# Ethernet.net
KiCad netlist of a schematic drawn in Altium Designer
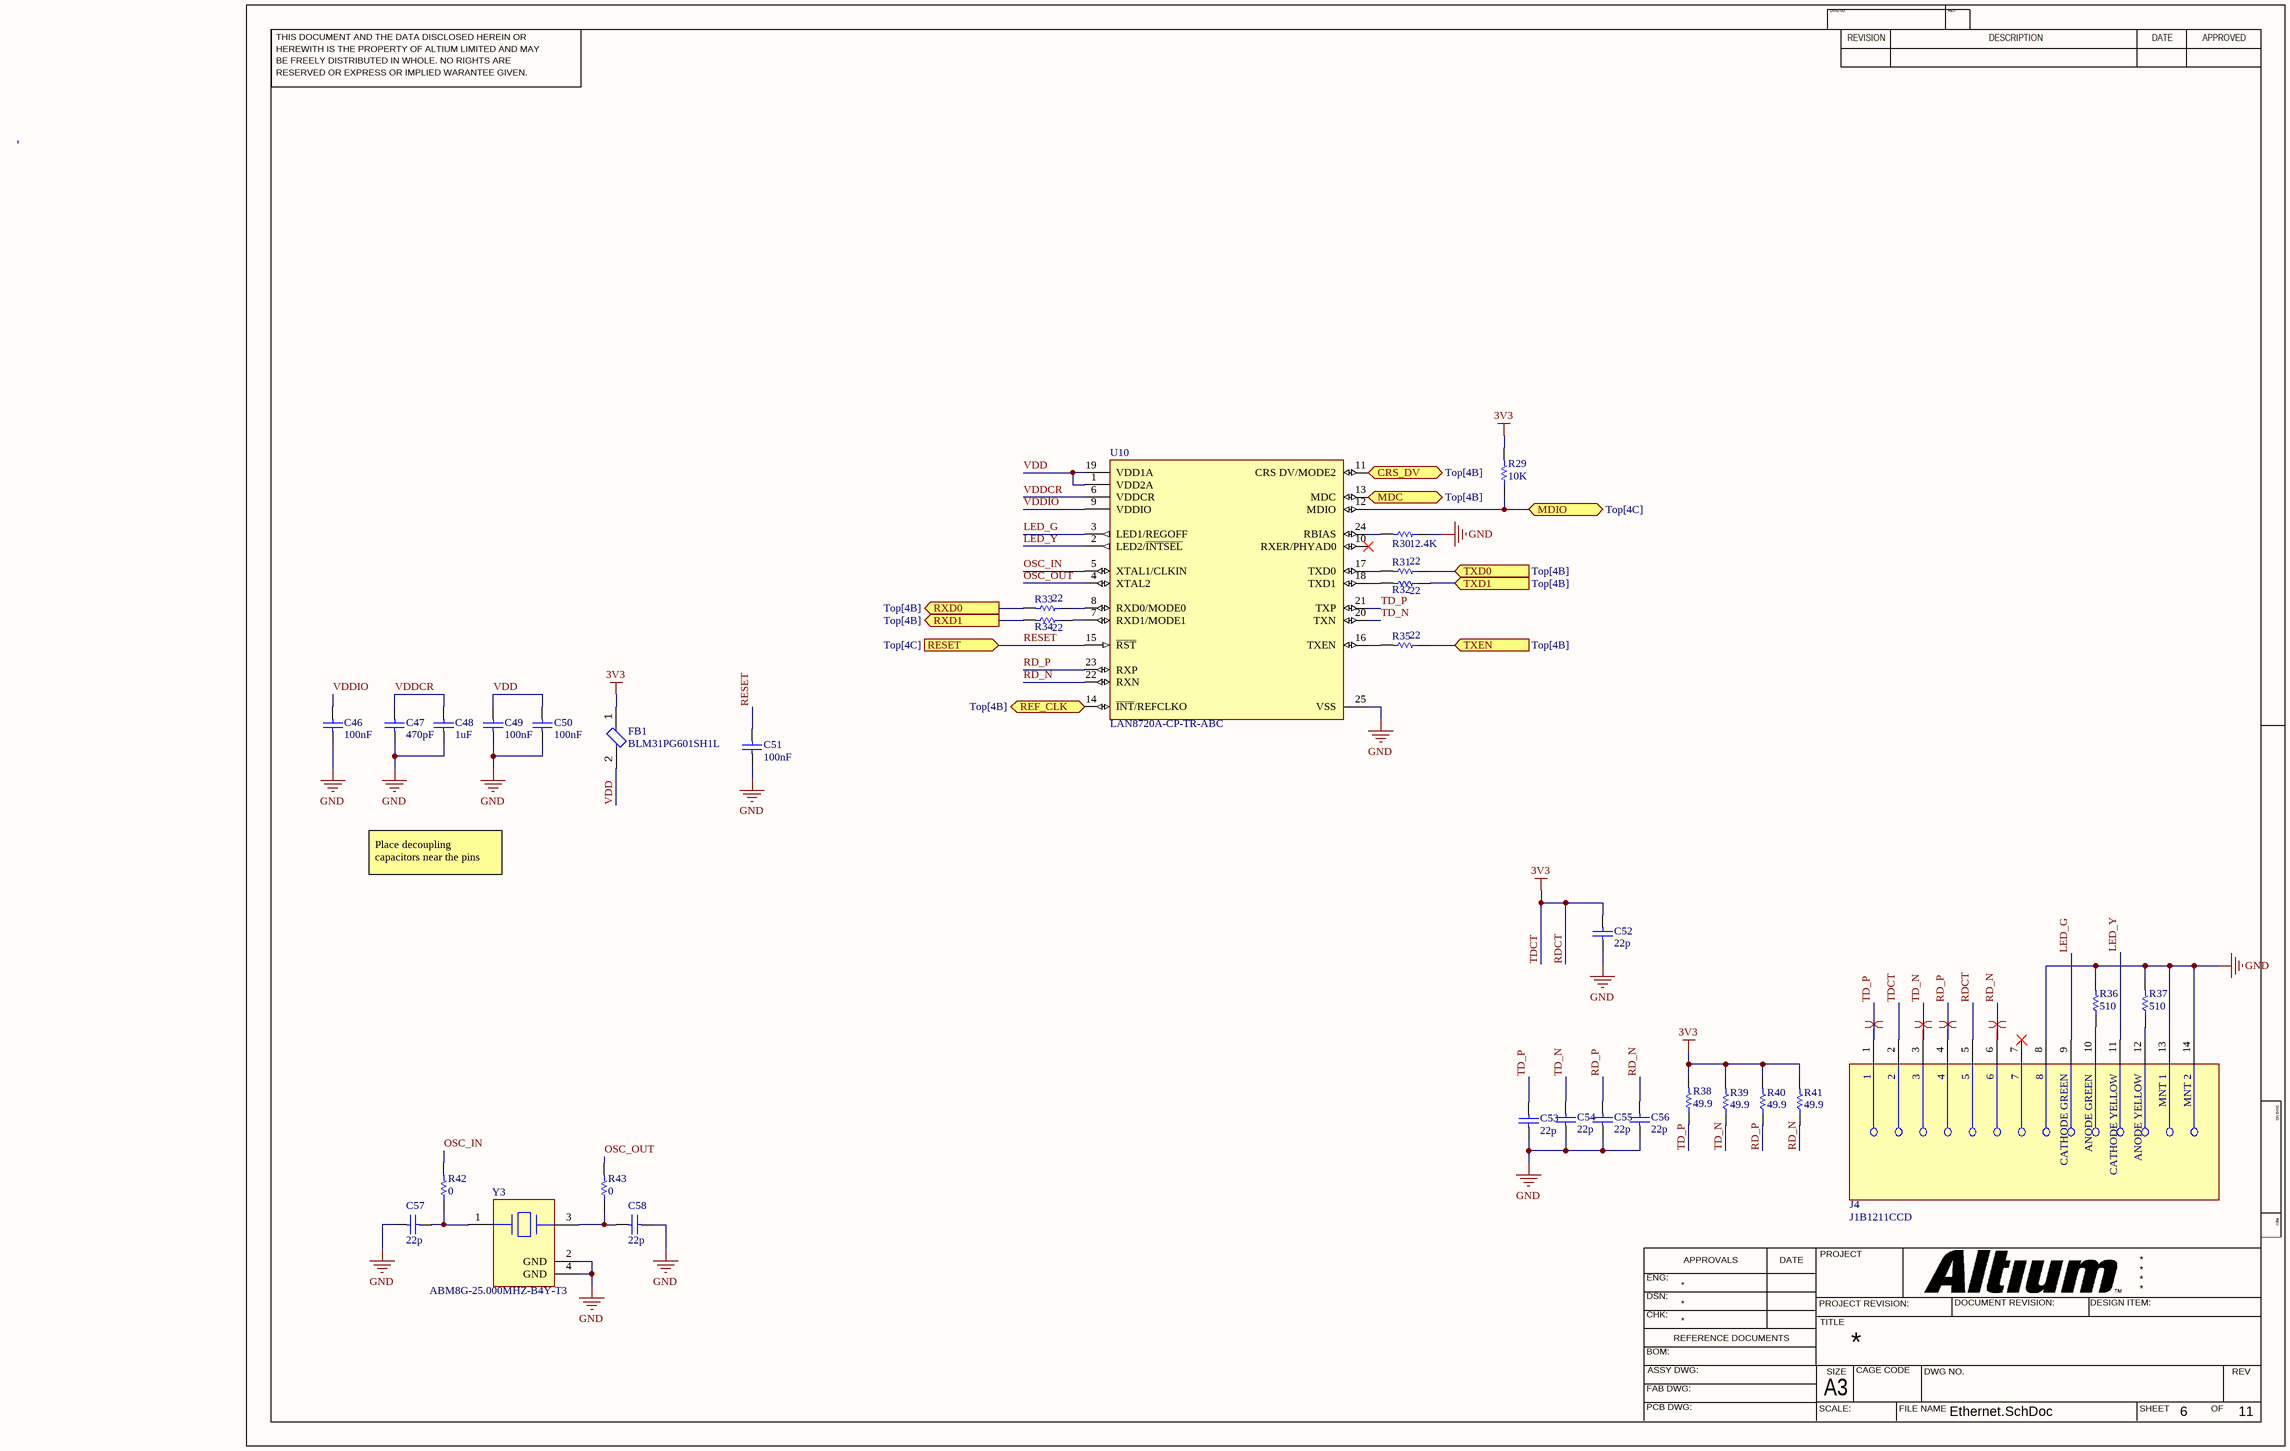
[diagram p0: Ethernet.SchDoc]

(export (version "E")
  (design (tool "Eeschema 10.0.6"))
  (components
    (comp (ref "C46")
      (value "100nF")
      (description "Capacitor")
      (libsource (lib "Simulation Generic Components") (part "Capacitor"))
    )
    (comp (ref "C47")
      (value "470pF")
      (description "Capacitor")
      (libsource (lib "Simulation Generic Components") (part "Capacitor"))
    )
    (comp (ref "C48")
      (value "1uF")
      (description "Capacitor")
      (libsource (lib "Simulation Generic Components") (part "Capacitor"))
    )
    (comp (ref "C49")
      (value "100nF")
      (description "Capacitor")
      (libsource (lib "Simulation Generic Components") (part "Capacitor"))
    )
    (comp (ref "C50")
      (value "100nF")
      (description "Capacitor")
      (libsource (lib "Simulation Generic Components") (part "Capacitor"))
    )
    (comp (ref "C51")
      (value "100nF")
      (description "Capacitor")
      (libsource (lib "Simulation Generic Components") (part "Capacitor"))
    )
    (comp (ref "C52")
      (value "22p")
      (description "Capacitor")
      (libsource (lib "Simulation Generic Components") (part "Capacitor"))
    )
    (comp (ref "C53")
      (value "22p")
      (description "Capacitor")
      (libsource (lib "Simulation Generic Components") (part "Capacitor"))
    )
    (comp (ref "C54")
      (value "22p")
      (description "Capacitor")
      (libsource (lib "Simulation Generic Components") (part "Capacitor"))
    )
    (comp (ref "C55")
      (value "22p")
      (description "Capacitor")
      (libsource (lib "Simulation Generic Components") (part "Capacitor"))
    )
    (comp (ref "C56")
      (value "22p")
      (description "Capacitor")
      (libsource (lib "Simulation Generic Components") (part "Capacitor"))
    )
    (comp (ref "C57")
      (value "22p")
      (description "Capacitor")
      (libsource (lib "Simulation Generic Components") (part "Capacitor"))
    )
    (comp (ref "C58")
      (value "22p")
      (description "Capacitor")
      (libsource (lib "Simulation Generic Components") (part "Capacitor"))
    )
    (comp (ref "FB1")
      (value "BLM31PG601SH1L")
      (footprint "FP-BLM31-0_2-t1_1-MFG")
      (description "Chip Ferrite Bead Array, 1206, 600Ω @ 100MHz, 0.08Ω, 25%, 1.5A")
      (fields (field (name "TOLERANCE") "25%"))
      (libsource (lib "Altium Content Vault") (part "5f30dd21d616792df468990f7003faa"))
    )
    (comp (ref "J4")
      (value "J1B1211CCD")
      (footprint "FP-J1B1211CCD-MFG")
      (description "CONN JACK 1PORT 100 BASE-T PCB")
      (libsource (lib "Altium Content Vault") (part "043a9053fb366fe6dc2bf5dbfb72c80"))
    )
    (comp (ref "R29")
      (value "10K")
      (description "Resistor")
      (libsource (lib "Simulation Generic Components") (part "Resistor"))
    )
    (comp (ref "R30")
      (value "12.4K")
      (description "Resistor")
      (libsource (lib "Simulation Generic Components") (part "Resistor"))
    )
    (comp (ref "R31")
      (value "22")
      (description "Resistor")
      (libsource (lib "Simulation Generic Components") (part "Resistor"))
    )
    (comp (ref "R32")
      (value "22")
      (description "Resistor")
      (libsource (lib "Simulation Generic Components") (part "Resistor"))
    )
    (comp (ref "R33")
      (value "22")
      (description "Resistor")
      (libsource (lib "Simulation Generic Components") (part "Resistor"))
    )
    (comp (ref "R34")
      (value "22")
      (description "Resistor")
      (libsource (lib "Simulation Generic Components") (part "Resistor"))
    )
    (comp (ref "R35")
      (value "22")
      (description "Resistor")
      (libsource (lib "Simulation Generic Components") (part "Resistor"))
    )
    (comp (ref "R36")
      (value "510")
      (description "Resistor")
      (libsource (lib "Simulation Generic Components") (part "Resistor"))
    )
    (comp (ref "R37")
      (value "510")
      (description "Resistor")
      (libsource (lib "Simulation Generic Components") (part "Resistor"))
    )
    (comp (ref "R38")
      (value "49.9")
      (description "Resistor")
      (libsource (lib "Simulation Generic Components") (part "Resistor"))
    )
    (comp (ref "R39")
      (value "49.9")
      (description "Resistor")
      (libsource (lib "Simulation Generic Components") (part "Resistor"))
    )
    (comp (ref "R40")
      (value "49.9")
      (description "Resistor")
      (libsource (lib "Simulation Generic Components") (part "Resistor"))
    )
    (comp (ref "R41")
      (value "49.9")
      (description "Resistor")
      (libsource (lib "Simulation Generic Components") (part "Resistor"))
    )
    (comp (ref "R42")
      (value "0")
      (description "Resistor")
      (libsource (lib "Simulation Generic Components") (part "Resistor"))
    )
    (comp (ref "R43")
      (value "0")
      (description "Resistor")
      (libsource (lib "Simulation Generic Components") (part "Resistor"))
    )
    (comp (ref "U10")
      (value "LAN8720A-CP-TR-ABC")
      (footprint "FP-24-S4QFN-4x4B-0_5P-IPC_B")
      (description "IC TRANSCEIVER FULL 2/2 24SQFN")
      (libsource (lib "Altium Content Vault") (part "9fc9cb1ae97c4b8e8fc1e70f7f78ae1"))
    )
    (comp (ref "Y3")
      (value "ABM8G-25.000MHZ-B4Y-T3")
      (footprint "FP-ABM8G-MFG")
      (description "Crystal 25MHz ±30ppm (Tol) ±30ppm (Stability) 10pF FUND 60Ω 4-Pin SMD T/R")
      (fields (field (name "TOLERANCE") "30ppm"))
      (libsource (lib "Altium Content Vault") (part "48e526d86b7f2615d98721063c72f49"))
    )
  )
  (nets
    (net (code "1") (name "/CRS_DV") (class "Default")
      (node (ref "U10") (pin "11") (pinfunction "CRS_DV/MODE2_11") (pintype "bidirectional"))
    )
    (net (code "2") (name "/LED_G") (class "Default")
      (node (ref "J4") (pin "9") (pinfunction "CATHODE_GREEN_9") (pintype "passive"))
      (node (ref "U10") (pin "3") (pinfunction "LED1/REGOFF_3") (pintype "output"))
    )
    (net (code "3") (name "/LED_Y") (class "Default")
      (node (ref "J4") (pin "11") (pinfunction "CATHODE_YELLOW_11") (pintype "passive"))
      (node (ref "U10") (pin "2") (pinfunction "LED2/~{INTSEL}_2") (pintype "output"))
    )
    (net (code "4") (name "/MDC") (class "Default")
      (node (ref "U10") (pin "13") (pinfunction "MDC_13") (pintype "bidirectional"))
    )
    (net (code "5") (name "/MDIO") (class "Default")
      (node (ref "R29") (pin "1") (pinfunction "1_1") (pintype "passive"))
      (node (ref "U10") (pin "12") (pinfunction "MDIO_12") (pintype "bidirectional"))
    )
    (net (code "6") (name "/OSC_IN") (class "Default")
      (node (ref "R42") (pin "2") (pinfunction "2_2") (pintype "passive"))
      (node (ref "U10") (pin "5") (pinfunction "XTAL1/CLKIN_5") (pintype "bidirectional"))
    )
    (net (code "7") (name "/OSC_OUT") (class "Default")
      (node (ref "R43") (pin "2") (pinfunction "2_2") (pintype "passive"))
      (node (ref "U10") (pin "4") (pinfunction "XTAL2_4") (pintype "bidirectional"))
    )
    (net (code "8") (name "/RD_N") (class "Default")
      (node (ref "C56") (pin "2") (pinfunction "2_2") (pintype "passive"))
      (node (ref "J4") (pin "6") (pinfunction "6_6") (pintype "passive"))
      (node (ref "R41") (pin "1") (pinfunction "1_1") (pintype "passive"))
      (node (ref "U10") (pin "22") (pinfunction "RXN_22") (pintype "bidirectional"))
    )
    (net (code "9") (name "/RD_P") (class "Default")
      (node (ref "C55") (pin "2") (pinfunction "2_2") (pintype "passive"))
      (node (ref "J4") (pin "4") (pinfunction "4_4") (pintype "passive"))
      (node (ref "R40") (pin "1") (pinfunction "1_1") (pintype "passive"))
      (node (ref "U10") (pin "23") (pinfunction "RXP_23") (pintype "bidirectional"))
    )
    (net (code "10") (name "/REF_CLK") (class "Default")
      (node (ref "U10") (pin "14") (pinfunction "~{INT}/REFCLKO_14") (pintype "bidirectional"))
    )
    (net (code "11") (name "/RESET") (class "Default")
      (node (ref "C51") (pin "2") (pinfunction "2_2") (pintype "passive"))
      (node (ref "U10") (pin "15") (pinfunction "~{RST}_15") (pintype "input"))
    )
    (net (code "12") (name "/RXD0") (class "Default")
      (node (ref "R33") (pin "2") (pinfunction "2_2") (pintype "passive"))
    )
    (net (code "13") (name "/RXD1") (class "Default")
      (node (ref "R34") (pin "2") (pinfunction "2_2") (pintype "passive"))
    )
    (net (code "14") (name "/TD_N") (class "Default")
      (node (ref "C54") (pin "2") (pinfunction "2_2") (pintype "passive"))
      (node (ref "J4") (pin "3") (pinfunction "3_3") (pintype "passive"))
      (node (ref "R39") (pin "1") (pinfunction "1_1") (pintype "passive"))
      (node (ref "U10") (pin "20") (pinfunction "TXN_20") (pintype "bidirectional"))
    )
    (net (code "15") (name "/TD_P") (class "Default")
      (node (ref "C53") (pin "2") (pinfunction "2_2") (pintype "passive"))
      (node (ref "J4") (pin "1") (pinfunction "1_1") (pintype "passive"))
      (node (ref "R38") (pin "1") (pinfunction "1_1") (pintype "passive"))
      (node (ref "U10") (pin "21") (pinfunction "TXP_21") (pintype "bidirectional"))
    )
    (net (code "16") (name "/TXD0") (class "Default")
      (node (ref "R31") (pin "1") (pinfunction "1_1") (pintype "passive"))
    )
    (net (code "17") (name "/TXD1") (class "Default")
      (node (ref "R32") (pin "1") (pinfunction "1_1") (pintype "passive"))
    )
    (net (code "18") (name "/TXEN") (class "Default")
      (node (ref "R35") (pin "1") (pinfunction "1_1") (pintype "passive"))
    )
    (net (code "19") (name "/VDD") (class "Default")
      (node (ref "C49") (pin "2") (pinfunction "2_2") (pintype "passive"))
      (node (ref "C50") (pin "2") (pinfunction "2_2") (pintype "passive"))
      (node (ref "FB1") (pin "2") (pinfunction "2_2") (pintype "passive"))
      (node (ref "U10") (pin "1") (pinfunction "VDD2A_1") (pintype "power_in"))
      (node (ref "U10") (pin "19") (pinfunction "VDD1A_19") (pintype "power_in"))
    )
    (net (code "20") (name "/VDDCR") (class "Default")
      (node (ref "C47") (pin "2") (pinfunction "2_2") (pintype "passive"))
      (node (ref "C48") (pin "2") (pinfunction "2_2") (pintype "passive"))
      (node (ref "U10") (pin "6") (pinfunction "VDDCR_6") (pintype "power_in"))
    )
    (net (code "21") (name "/VDDIO") (class "Default")
      (node (ref "C46") (pin "2") (pinfunction "2_2") (pintype "passive"))
      (node (ref "U10") (pin "9") (pinfunction "VDDIO_9") (pintype "power_in"))
    )
    (net (code "22") (name "3V3") (class "Default")
      (node (ref "C52") (pin "2") (pinfunction "2_2") (pintype "passive"))
      (node (ref "FB1") (pin "1") (pinfunction "1_1") (pintype "passive"))
      (node (ref "J4") (pin "2") (pinfunction "2_2") (pintype "passive"))
      (node (ref "J4") (pin "5") (pinfunction "5_5") (pintype "passive"))
      (node (ref "R29") (pin "2") (pinfunction "2_2") (pintype "passive"))
      (node (ref "R38") (pin "2") (pinfunction "2_2") (pintype "passive"))
      (node (ref "R39") (pin "2") (pinfunction "2_2") (pintype "passive"))
      (node (ref "R40") (pin "2") (pinfunction "2_2") (pintype "passive"))
      (node (ref "R41") (pin "2") (pinfunction "2_2") (pintype "passive"))
    )
    (net (code "23") (name "GND") (class "Default")
      (node (ref "C46") (pin "1") (pinfunction "1_1") (pintype "passive"))
      (node (ref "C47") (pin "1") (pinfunction "1_1") (pintype "passive"))
      (node (ref "C48") (pin "1") (pinfunction "1_1") (pintype "passive"))
      (node (ref "C49") (pin "1") (pinfunction "1_1") (pintype "passive"))
      (node (ref "C50") (pin "1") (pinfunction "1_1") (pintype "passive"))
      (node (ref "C51") (pin "1") (pinfunction "1_1") (pintype "passive"))
      (node (ref "C52") (pin "1") (pinfunction "1_1") (pintype "passive"))
      (node (ref "C53") (pin "1") (pinfunction "1_1") (pintype "passive"))
      (node (ref "C54") (pin "1") (pinfunction "1_1") (pintype "passive"))
      (node (ref "C55") (pin "1") (pinfunction "1_1") (pintype "passive"))
      (node (ref "C56") (pin "1") (pinfunction "1_1") (pintype "passive"))
      (node (ref "C57") (pin "2") (pinfunction "2_2") (pintype "passive"))
      (node (ref "C58") (pin "1") (pinfunction "1_1") (pintype "passive"))
      (node (ref "J4") (pin "13") (pinfunction "MNT_1_13") (pintype "passive"))
      (node (ref "J4") (pin "14") (pinfunction "MNT_2_14") (pintype "passive"))
      (node (ref "J4") (pin "8") (pinfunction "8_8") (pintype "passive"))
      (node (ref "R30") (pin "1") (pinfunction "1_1") (pintype "passive"))
      (node (ref "R36") (pin "2") (pinfunction "2_2") (pintype "passive"))
      (node (ref "R37") (pin "2") (pinfunction "2_2") (pintype "passive"))
      (node (ref "U10") (pin "25") (pinfunction "VSS_25") (pintype "power_in"))
      (node (ref "Y3") (pin "2") (pinfunction "GND_2") (pintype "power_in"))
      (node (ref "Y3") (pin "4") (pinfunction "GND_4") (pintype "power_in"))
    )
    (net (code "24") (name "Net-(C57-Pad1)") (class "Default")
      (node (ref "C57") (pin "1") (pinfunction "1_1") (pintype "passive"))
      (node (ref "R42") (pin "1") (pinfunction "1_1") (pintype "passive"))
      (node (ref "Y3") (pin "1") (pinfunction "1_1") (pintype "passive"))
    )
    (net (code "25") (name "Net-(C58-Pad2)") (class "Default")
      (node (ref "C58") (pin "2") (pinfunction "2_2") (pintype "passive"))
      (node (ref "R43") (pin "1") (pinfunction "1_1") (pintype "passive"))
      (node (ref "Y3") (pin "3") (pinfunction "3_3") (pintype "passive"))
    )
    (net (code "26") (name "Net-(J4-ANODE_GREEN)") (class "Default")
      (node (ref "J4") (pin "10") (pinfunction "ANODE_GREEN_10") (pintype "passive"))
      (node (ref "R36") (pin "1") (pinfunction "1_1") (pintype "passive"))
    )
    (net (code "27") (name "Net-(J4-ANODE_YELLOW)") (class "Default")
      (node (ref "J4") (pin "12") (pinfunction "ANODE_YELLOW_12") (pintype "passive"))
      (node (ref "R37") (pin "1") (pinfunction "1_1") (pintype "passive"))
    )
    (net (code "28") (name "Net-(U10-RBIAS)") (class "Default")
      (node (ref "R30") (pin "2") (pinfunction "2_2") (pintype "passive"))
      (node (ref "U10") (pin "24") (pinfunction "RBIAS_24") (pintype "bidirectional"))
    )
    (net (code "29") (name "Net-(U10-RXD0{slash}MODE0)") (class "Default")
      (node (ref "R33") (pin "1") (pinfunction "1_1") (pintype "passive"))
      (node (ref "U10") (pin "8") (pinfunction "RXD0/MODE0_8") (pintype "bidirectional"))
    )
    (net (code "30") (name "Net-(U10-RXD1{slash}MODE1)") (class "Default")
      (node (ref "R34") (pin "1") (pinfunction "1_1") (pintype "passive"))
      (node (ref "U10") (pin "7") (pinfunction "RXD1/MODE1_7") (pintype "bidirectional"))
    )
    (net (code "31") (name "Net-(U10-TXD0)") (class "Default")
      (node (ref "R31") (pin "2") (pinfunction "2_2") (pintype "passive"))
      (node (ref "U10") (pin "17") (pinfunction "TXD0_17") (pintype "bidirectional"))
    )
    (net (code "32") (name "Net-(U10-TXD1)") (class "Default")
      (node (ref "R32") (pin "2") (pinfunction "2_2") (pintype "passive"))
      (node (ref "U10") (pin "18") (pinfunction "TXD1_18") (pintype "bidirectional"))
    )
    (net (code "33") (name "Net-(U10-TXEN)") (class "Default")
      (node (ref "R35") (pin "2") (pinfunction "2_2") (pintype "passive"))
      (node (ref "U10") (pin "16") (pinfunction "TXEN_16") (pintype "bidirectional"))
    )
    (net (code "34") (name "unconnected-(J4-Pad7)") (class "Default")
      (node (ref "J4") (pin "7") (pinfunction "7_7") (pintype "passive+no_connect"))
    )
    (net (code "35") (name "unconnected-(U10-RXER{slash}PHYAD0-Pad10)") (class "Default")
      (node (ref "U10") (pin "10") (pinfunction "RXER/PHYAD0_10") (pintype "bidirectional+no_connect"))
    )
  )
)
